# BLE112_Breakout_Board_v2_2.net
KiCad netlist of a schematic drawn in EAGLE
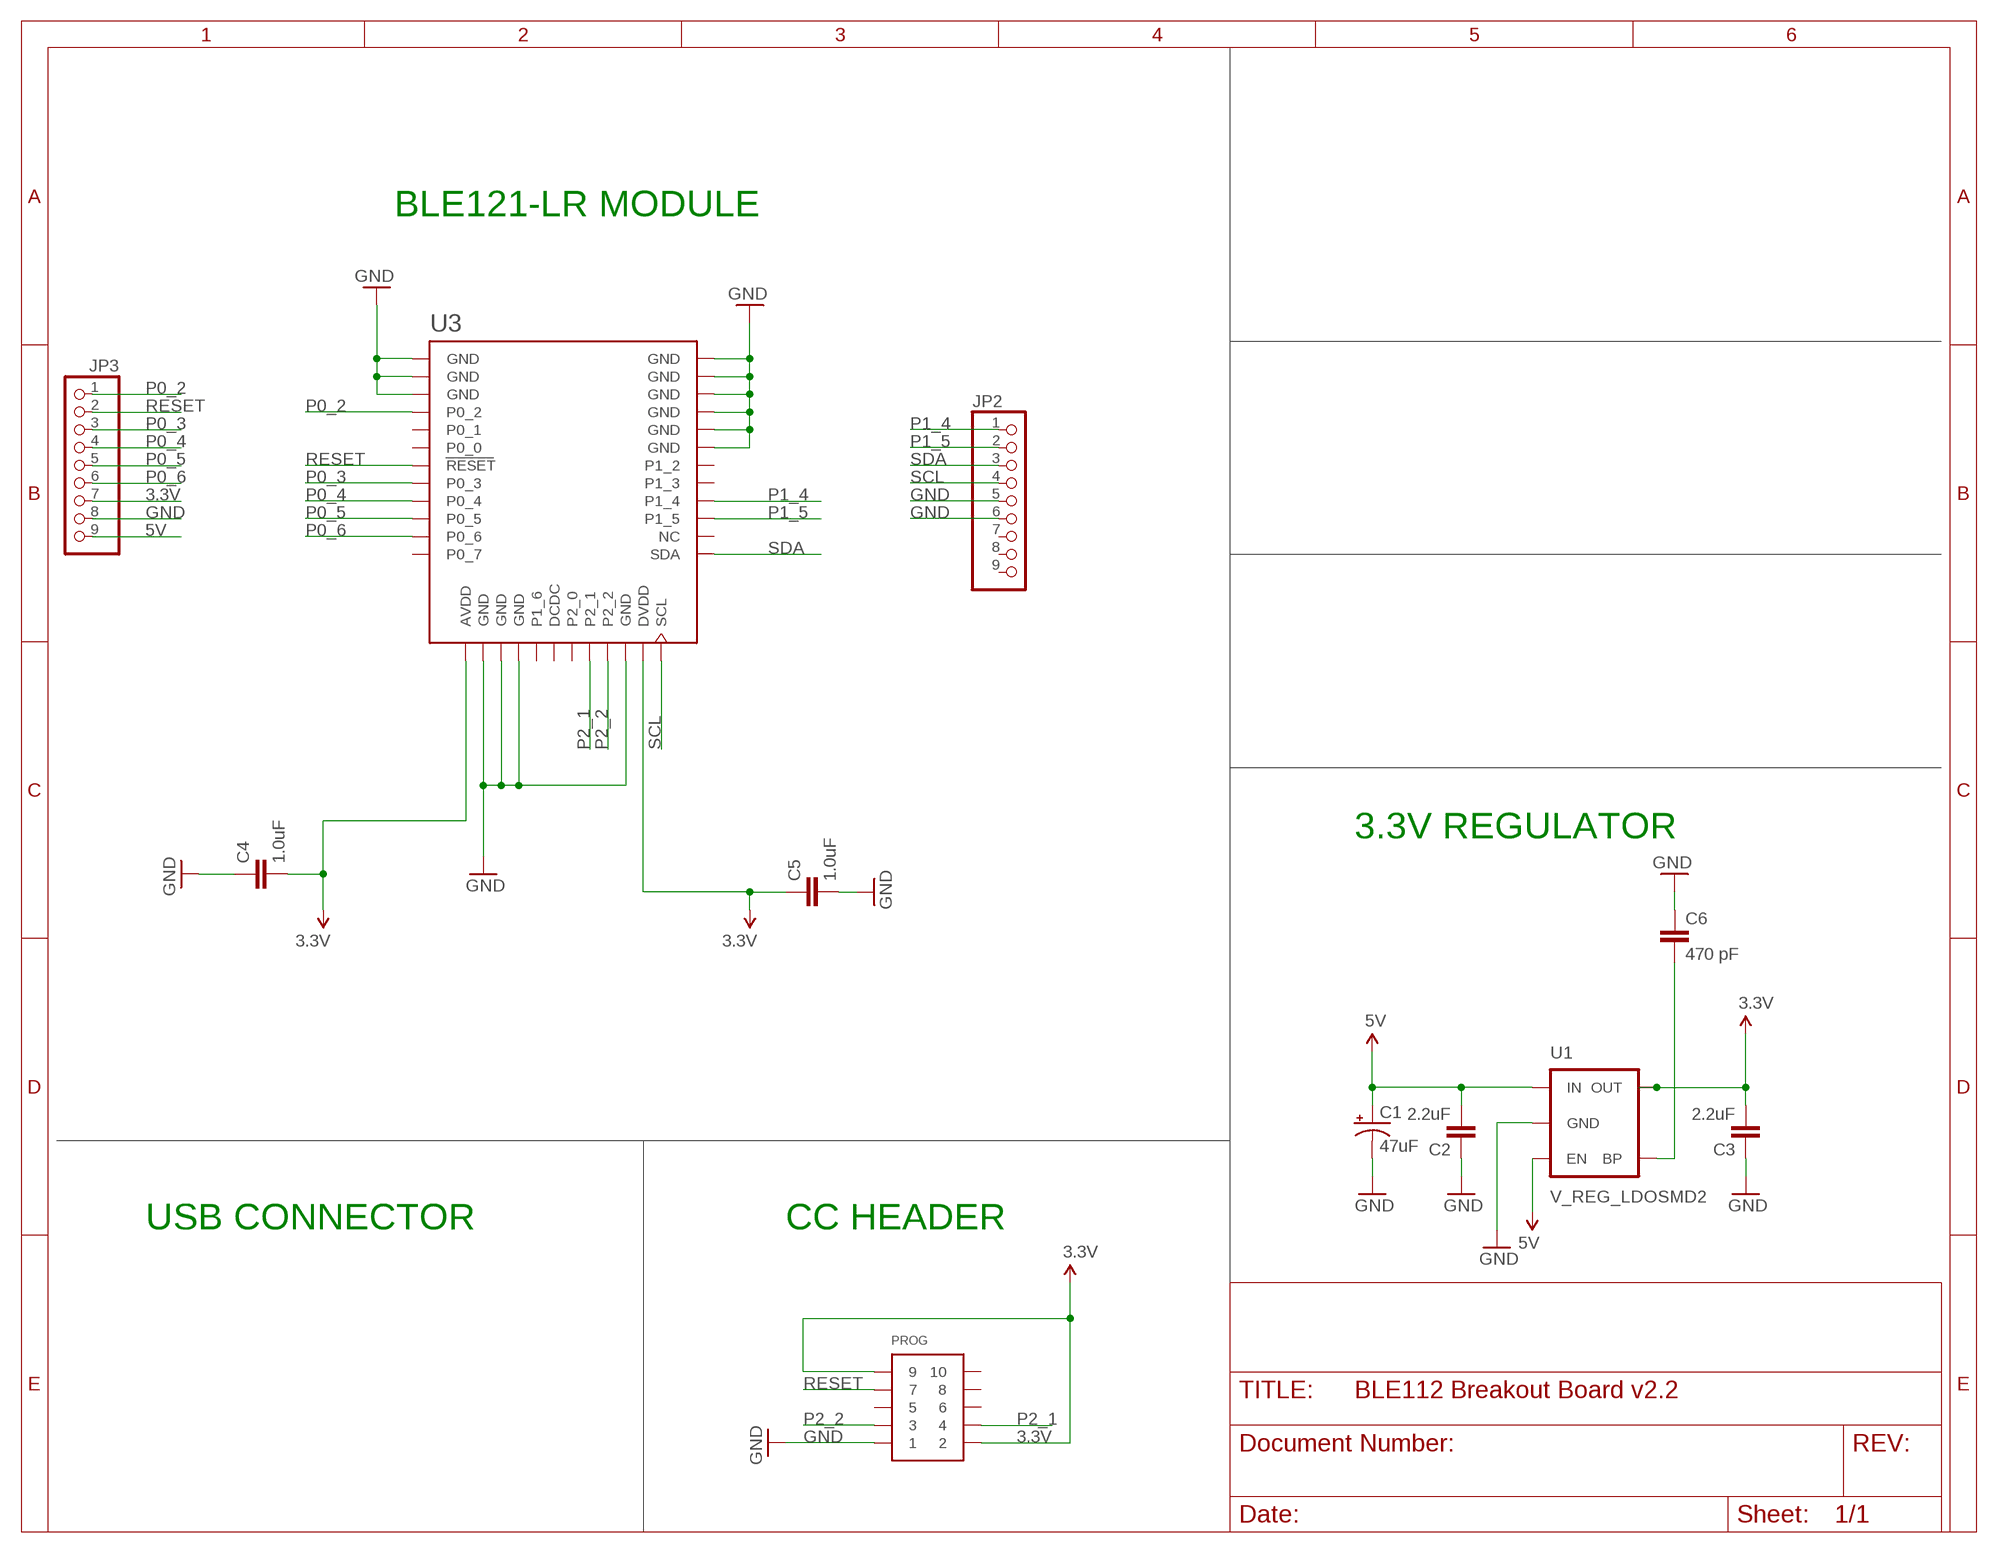
[diagram p0: schematic, sheet 1]

(export (version "E")
  (design (tool "Eeschema 10.0.6"))
  (components
    (comp (ref "C1")
      (value "47uF")
      (footprint "eagle-import:PANASONIC_D")
      (libsource (lib "eagle-import") (part "47UF-50V-20%(ELECT)"))
    )
    (comp (ref "C2")
      (value "2.2uF")
      (footprint "eagle-import:0402-CAP")
      (libsource (lib "eagle-import") (part "1.0UF-16V-10%(0402)"))
    )
    (comp (ref "C3")
      (value "2.2uF")
      (footprint "eagle-import:0402-CAP")
      (libsource (lib "eagle-import") (part "1.0UF-16V-10%(0402)"))
    )
    (comp (ref "C4")
      (value "1.0uF")
      (footprint "eagle-import:0402-CAP")
      (libsource (lib "eagle-import") (part "1.0UF-16V-10%(0402)"))
    )
    (comp (ref "C5")
      (value "1.0uF")
      (footprint "eagle-import:0402-CAP")
      (libsource (lib "eagle-import") (part "1.0UF-16V-10%(0402)"))
    )
    (comp (ref "C6")
      (value "470 pF")
      (footprint "eagle-import:0402-CAP")
      (libsource (lib "eagle-import") (part "CAP0402-CAP"))
    )
    (comp (ref "JP2")
      (value "PINHD-1X9")
      (footprint "eagle-import:1X09-BIG")
      (libsource (lib "eagle-import") (part "PINHD-1X9"))
    )
    (comp (ref "JP3")
      (value "PINHD-1X9")
      (footprint "eagle-import:1X09-BIG")
      (libsource (lib "eagle-import") (part "PINHD-1X9"))
    )
    (comp (ref "PROG")
      (value "CONN_5-2-FTSH-V")
      (footprint "eagle-import:FTSH-105-DV")
      (libsource (lib "eagle-import") (part "CONN_5-2-FTSH-V"))
    )
    (comp (ref "U1")
      (value "V_REG_LDOSMD2")
      (footprint "eagle-import:SC70")
      (libsource (lib "eagle-import") (part "V_REG_LDOSMD2"))
    )
    (comp (ref "U3")
      (value "BLE121LR-VISUAL-A")
      (footprint "eagle-import:BLE121LR-A")
      (libsource (lib "eagle-import") (part "BLE121LR-VISUAL-A"))
    )
  )
  (nets
    (net (code "1") (name "/P0_2") (class "Default")
      (node (ref "JP3") (pin "1") (pinfunction "1_1") (pintype "passive"))
      (node (ref "U3") (pin "P0_2") (pinfunction "P0_2_P0_2") (pintype "bidirectional"))
    )
    (net (code "2") (name "/P0_3") (class "Default")
      (node (ref "JP3") (pin "3") (pinfunction "3_3") (pintype "passive"))
      (node (ref "U3") (pin "P0_3") (pinfunction "P0_3_P0_3") (pintype "bidirectional"))
    )
    (net (code "3") (name "/P0_4") (class "Default")
      (node (ref "JP3") (pin "4") (pinfunction "4_4") (pintype "passive"))
      (node (ref "U3") (pin "P0_4") (pinfunction "P0_4_P0_4") (pintype "bidirectional"))
    )
    (net (code "4") (name "/P0_5") (class "Default")
      (node (ref "JP3") (pin "5") (pinfunction "5_5") (pintype "passive"))
      (node (ref "U3") (pin "P0_5") (pinfunction "P0_5_P0_5") (pintype "bidirectional"))
    )
    (net (code "5") (name "/P0_6") (class "Default")
      (node (ref "JP3") (pin "6") (pinfunction "6_6") (pintype "passive"))
      (node (ref "U3") (pin "P0_6") (pinfunction "P0_6_P0_6") (pintype "bidirectional"))
    )
    (net (code "6") (name "/P1_4") (class "Default")
      (node (ref "JP2") (pin "1") (pinfunction "1_1") (pintype "passive"))
      (node (ref "U3") (pin "P1_4") (pinfunction "P1_4_P1_4") (pintype "bidirectional"))
    )
    (net (code "7") (name "/P1_5") (class "Default")
      (node (ref "JP2") (pin "2") (pinfunction "2_2") (pintype "passive"))
      (node (ref "U3") (pin "P1_5") (pinfunction "P1_5_P1_5") (pintype "bidirectional"))
    )
    (net (code "8") (name "/P2_1") (class "Default")
      (node (ref "PROG") (pin "4") (pinfunction "4_4") (pintype "bidirectional"))
      (node (ref "U3") (pin "P2_1") (pinfunction "P2_1_P2_1") (pintype "bidirectional"))
    )
    (net (code "9") (name "/P2_2") (class "Default")
      (node (ref "PROG") (pin "3") (pinfunction "3_3") (pintype "bidirectional"))
      (node (ref "U3") (pin "P2_2") (pinfunction "P2_2_P2_2") (pintype "bidirectional"))
    )
    (net (code "10") (name "/RESET") (class "Default")
      (node (ref "JP3") (pin "2") (pinfunction "2_2") (pintype "passive"))
      (node (ref "PROG") (pin "7") (pinfunction "7_7") (pintype "bidirectional"))
      (node (ref "U3") (pin "RESET") (pinfunction "RESET_RESET") (pintype "input"))
    )
    (net (code "11") (name "/SCL") (class "Default")
      (node (ref "JP2") (pin "4") (pinfunction "4_4") (pintype "passive"))
      (node (ref "U3") (pin "SCL") (pinfunction "SCL_SCL") (pintype "bidirectional"))
    )
    (net (code "12") (name "/SDA") (class "Default")
      (node (ref "JP2") (pin "3") (pinfunction "3_3") (pintype "passive"))
      (node (ref "U3") (pin "SDA") (pinfunction "SDA_SDA") (pintype "bidirectional"))
    )
    (net (code "13") (name "3.3V") (class "Default")
      (node (ref "C3") (pin "2") (pinfunction "2_2") (pintype "passive"))
      (node (ref "C4") (pin "2") (pinfunction "2_2") (pintype "passive"))
      (node (ref "C5") (pin "1") (pinfunction "1_1") (pintype "passive"))
      (node (ref "JP3") (pin "7") (pinfunction "7_7") (pintype "passive"))
      (node (ref "PROG") (pin "2") (pinfunction "2_2") (pintype "bidirectional"))
      (node (ref "PROG") (pin "9") (pinfunction "9_9") (pintype "bidirectional"))
      (node (ref "U1") (pin "5") (pinfunction "OUT_5") (pintype "passive"))
      (node (ref "U3") (pin "AVDD") (pinfunction "AVDD_AVDD") (pintype "power_in"))
      (node (ref "U3") (pin "DVDD") (pinfunction "DVDD_DVDD") (pintype "power_in"))
    )
    (net (code "14") (name "5V") (class "Default")
      (node (ref "C1") (pin "+") (pinfunction "+_+") (pintype "passive"))
      (node (ref "C2") (pin "2") (pinfunction "2_2") (pintype "passive"))
      (node (ref "JP3") (pin "9") (pinfunction "9_9") (pintype "passive"))
      (node (ref "U1") (pin "1") (pinfunction "IN_1") (pintype "input"))
      (node (ref "U1") (pin "3") (pinfunction "EN_3") (pintype "input"))
    )
    (net (code "15") (name "GND") (class "Default")
      (node (ref "C1") (pin "-") (pinfunction "-_-") (pintype "passive"))
      (node (ref "C2") (pin "1") (pinfunction "1_1") (pintype "passive"))
      (node (ref "C3") (pin "1") (pinfunction "1_1") (pintype "passive"))
      (node (ref "C4") (pin "1") (pinfunction "1_1") (pintype "passive"))
      (node (ref "C5") (pin "2") (pinfunction "2_2") (pintype "passive"))
      (node (ref "C6") (pin "1") (pinfunction "1_1") (pintype "passive"))
      (node (ref "JP2") (pin "5") (pinfunction "5_5") (pintype "passive"))
      (node (ref "JP2") (pin "6") (pinfunction "6_6") (pintype "passive"))
      (node (ref "JP3") (pin "8") (pinfunction "8_8") (pintype "passive"))
      (node (ref "PROG") (pin "1") (pinfunction "1_1") (pintype "bidirectional"))
      (node (ref "U1") (pin "2") (pinfunction "GND_2") (pintype "input"))
      (node (ref "U3") (pin "GND") (pinfunction "GND_GND") (pintype "power_in"))
      (node (ref "U3") (pin "GND@10") (pinfunction "GND_GND@10") (pintype "power_in"))
      (node (ref "U3") (pin "GND@11") (pinfunction "GND_GND@11") (pintype "power_in"))
      (node (ref "U3") (pin "GND@12") (pinfunction "GND_GND@12") (pintype "power_in"))
      (node (ref "U3") (pin "GND@13") (pinfunction "GND_GND@13") (pintype "power_in"))
      (node (ref "U3") (pin "GND@2") (pinfunction "GND_GND@2") (pintype "power_in"))
      (node (ref "U3") (pin "GND@3") (pinfunction "GND_GND@3") (pintype "power_in"))
      (node (ref "U3") (pin "GND@4") (pinfunction "GND_GND@4") (pintype "power_in"))
      (node (ref "U3") (pin "GND@5") (pinfunction "GND_GND@5") (pintype "power_in"))
      (node (ref "U3") (pin "GND@6") (pinfunction "GND_GND@6") (pintype "power_in"))
      (node (ref "U3") (pin "GND@7") (pinfunction "GND_GND@7") (pintype "power_in"))
      (node (ref "U3") (pin "GND@8") (pinfunction "GND_GND@8") (pintype "power_in"))
      (node (ref "U3") (pin "GND@9") (pinfunction "GND_GND@9") (pintype "power_in"))
    )
    (net (code "16") (name "Net-(U1-BP)") (class "Default")
      (node (ref "C6") (pin "2") (pinfunction "2_2") (pintype "passive"))
      (node (ref "U1") (pin "4") (pinfunction "BP_4") (pintype "input"))
    )
    (net (code "17") (name "unconnected-(JP2-Pad7)") (class "Default")
      (node (ref "JP2") (pin "7") (pinfunction "7_7") (pintype "passive"))
    )
    (net (code "18") (name "unconnected-(JP2-Pad8)") (class "Default")
      (node (ref "JP2") (pin "8") (pinfunction "8_8") (pintype "passive"))
    )
    (net (code "19") (name "unconnected-(JP2-Pad9)") (class "Default")
      (node (ref "JP2") (pin "9") (pinfunction "9_9") (pintype "passive"))
    )
    (net (code "20") (name "unconnected-(PROG-Pad5)") (class "Default")
      (node (ref "PROG") (pin "5") (pinfunction "5_5") (pintype "bidirectional"))
    )
    (net (code "21") (name "unconnected-(PROG-Pad6)") (class "Default")
      (node (ref "PROG") (pin "6") (pinfunction "6_6") (pintype "bidirectional"))
    )
    (net (code "22") (name "unconnected-(PROG-Pad8)") (class "Default")
      (node (ref "PROG") (pin "8") (pinfunction "8_8") (pintype "bidirectional"))
    )
    (net (code "23") (name "unconnected-(PROG-Pad10)") (class "Default")
      (node (ref "PROG") (pin "10") (pinfunction "10_10") (pintype "bidirectional"))
    )
    (net (code "24") (name "unconnected-(U3-PadDCDC)") (class "Default")
      (node (ref "U3") (pin "DCDC") (pinfunction "DCDC_DCDC") (pintype "bidirectional"))
    )
    (net (code "25") (name "unconnected-(U3-PadNC)") (class "Default")
      (node (ref "U3") (pin "NC") (pinfunction "NC_NC") (pintype "no_connect"))
    )
    (net (code "26") (name "unconnected-(U3-PadP0_0)") (class "Default")
      (node (ref "U3") (pin "P0_0") (pinfunction "P0_0_P0_0") (pintype "bidirectional"))
    )
    (net (code "27") (name "unconnected-(U3-PadP0_1)") (class "Default")
      (node (ref "U3") (pin "P0_1") (pinfunction "P0_1_P0_1") (pintype "bidirectional"))
    )
    (net (code "28") (name "unconnected-(U3-PadP0_7)") (class "Default")
      (node (ref "U3") (pin "P0_7") (pinfunction "P0_7_P0_7") (pintype "bidirectional"))
    )
    (net (code "29") (name "unconnected-(U3-PadP1_2)") (class "Default")
      (node (ref "U3") (pin "P1_2") (pinfunction "P1_2_P1_2") (pintype "bidirectional"))
    )
    (net (code "30") (name "unconnected-(U3-PadP1_3)") (class "Default")
      (node (ref "U3") (pin "P1_3") (pinfunction "P1_3_P1_3") (pintype "bidirectional"))
    )
    (net (code "31") (name "unconnected-(U3-PadP1_6)") (class "Default")
      (node (ref "U3") (pin "P1_6") (pinfunction "P1_6_P1_6") (pintype "bidirectional"))
    )
    (net (code "32") (name "unconnected-(U3-PadP2_0)") (class "Default")
      (node (ref "U3") (pin "P2_0") (pinfunction "P2_0_P2_0") (pintype "bidirectional"))
    )
  )
)
